# module-pam8320.net
KiCad netlist of a schematic drawn in EAGLE
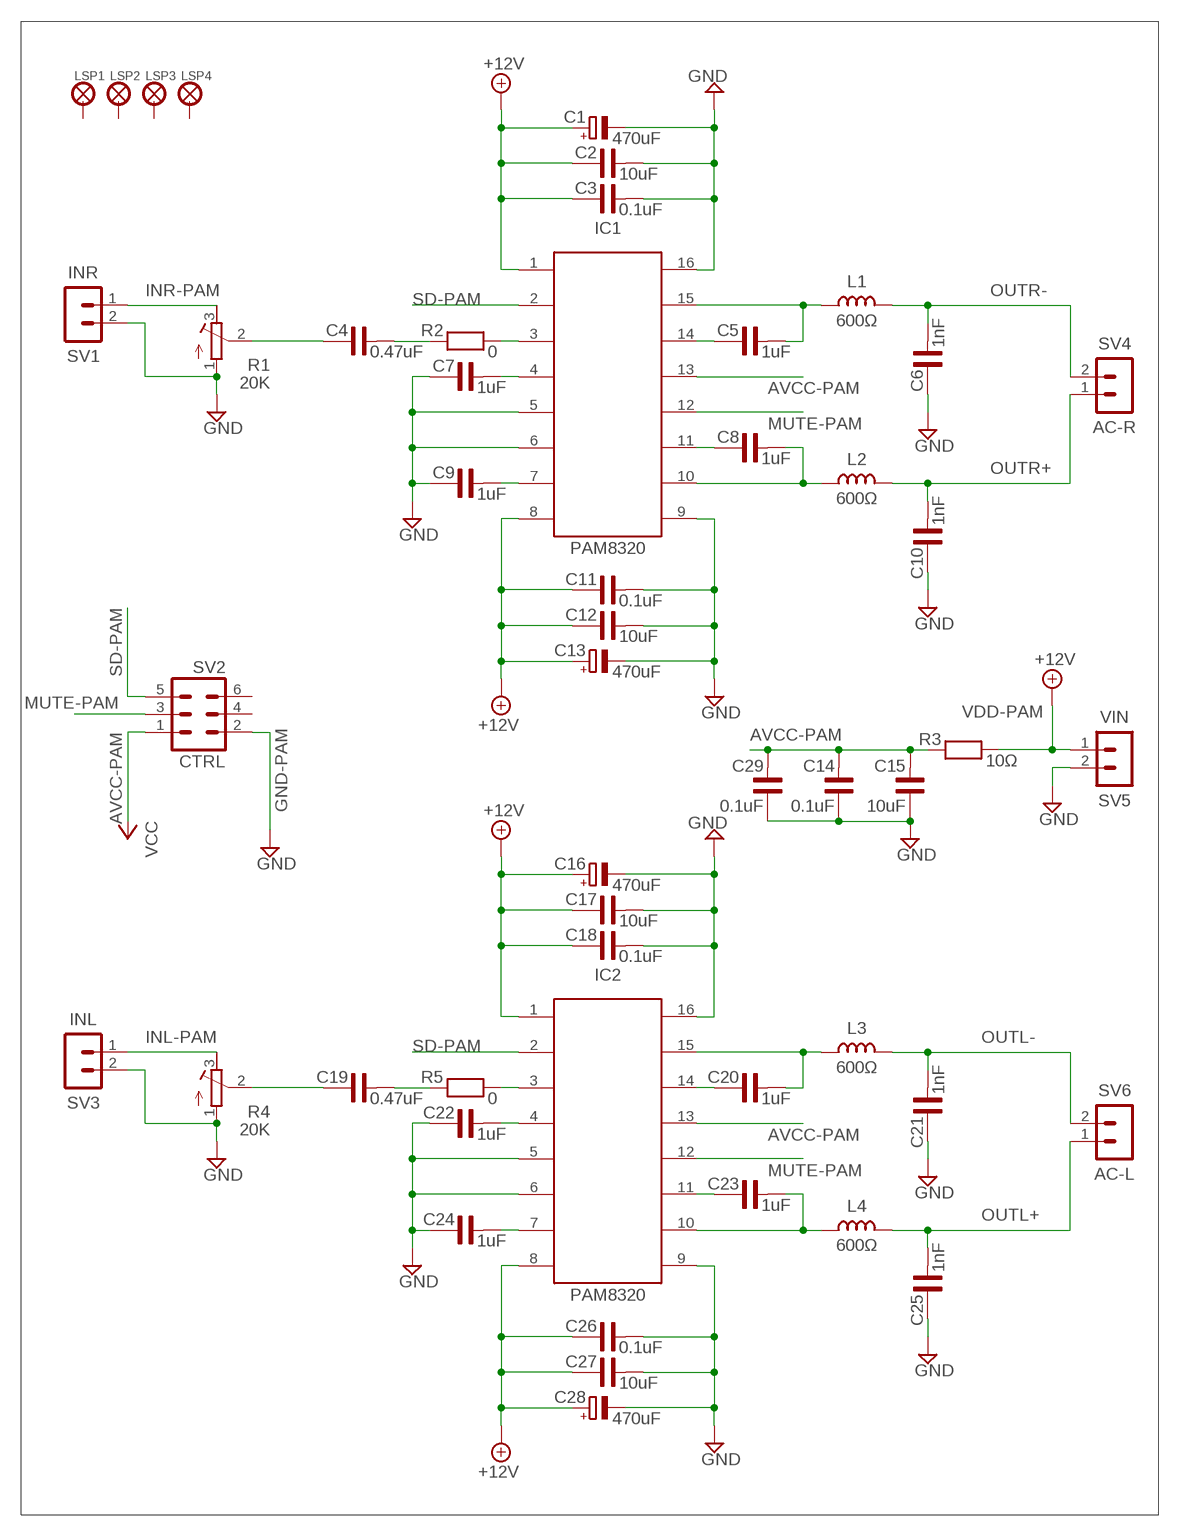
[diagram p0: schematic, sheet 1]

(export (version "E")
  (design (tool "Eeschema 10.0.6"))
  (components
    (comp (ref "C1")
      (value "470uF")
      (footprint "eagle-import:E5-10,5")
      (libsource (lib "eagle-import") (part "CPOL-EUE5-10.5"))
    )
    (comp (ref "C2")
      (value "10uF")
      (footprint "eagle-import:C1206")
      (libsource (lib "eagle-import") (part "C-US1206"))
    )
    (comp (ref "C3")
      (value "0.1uF")
      (footprint "eagle-import:C0805")
      (libsource (lib "eagle-import") (part "C-US0805"))
    )
    (comp (ref "C4")
      (value "0.47uF")
      (footprint "eagle-import:C0805")
      (libsource (lib "eagle-import") (part "C-US0805"))
    )
    (comp (ref "C5")
      (value "1uF")
      (footprint "eagle-import:C1206")
      (libsource (lib "eagle-import") (part "C-US1206"))
    )
    (comp (ref "C6")
      (value "1nF")
      (footprint "eagle-import:C0805")
      (libsource (lib "eagle-import") (part "C-US0805"))
    )
    (comp (ref "C7")
      (value "1uF")
      (footprint "eagle-import:C1206")
      (libsource (lib "eagle-import") (part "C-US1206"))
    )
    (comp (ref "C8")
      (value "1uF")
      (footprint "eagle-import:C1206")
      (libsource (lib "eagle-import") (part "C-US1206"))
    )
    (comp (ref "C9")
      (value "1uF")
      (footprint "eagle-import:C1206")
      (libsource (lib "eagle-import") (part "C-US1206"))
    )
    (comp (ref "C10")
      (value "1nF")
      (footprint "eagle-import:C0805")
      (libsource (lib "eagle-import") (part "C-US0805"))
    )
    (comp (ref "C11")
      (value "0.1uF")
      (footprint "eagle-import:C0805")
      (libsource (lib "eagle-import") (part "C-US0805"))
    )
    (comp (ref "C12")
      (value "10uF")
      (footprint "eagle-import:C1206")
      (libsource (lib "eagle-import") (part "C-US1206"))
    )
    (comp (ref "C13")
      (value "470uF")
      (footprint "eagle-import:E5-10,5")
      (libsource (lib "eagle-import") (part "CPOL-EUE5-10.5"))
    )
    (comp (ref "C14")
      (value "0.1uF")
      (footprint "eagle-import:C0805")
      (libsource (lib "eagle-import") (part "C-US0805"))
    )
    (comp (ref "C15")
      (value "10uF")
      (footprint "eagle-import:C1206")
      (libsource (lib "eagle-import") (part "C-US1206"))
    )
    (comp (ref "C16")
      (value "470uF")
      (footprint "eagle-import:E5-10,5")
      (libsource (lib "eagle-import") (part "CPOL-EUE5-10.5"))
    )
    (comp (ref "C17")
      (value "10uF")
      (footprint "eagle-import:C1206")
      (libsource (lib "eagle-import") (part "C-US1206"))
    )
    (comp (ref "C18")
      (value "0.1uF")
      (footprint "eagle-import:C0805")
      (libsource (lib "eagle-import") (part "C-US0805"))
    )
    (comp (ref "C19")
      (value "0.47uF")
      (footprint "eagle-import:C0805")
      (libsource (lib "eagle-import") (part "C-US0805"))
    )
    (comp (ref "C20")
      (value "1uF")
      (footprint "eagle-import:C1206")
      (libsource (lib "eagle-import") (part "C-US1206"))
    )
    (comp (ref "C21")
      (value "1nF")
      (footprint "eagle-import:C0805")
      (libsource (lib "eagle-import") (part "C-US0805"))
    )
    (comp (ref "C22")
      (value "1uF")
      (footprint "eagle-import:C1206")
      (libsource (lib "eagle-import") (part "C-US1206"))
    )
    (comp (ref "C23")
      (value "1uF")
      (footprint "eagle-import:C1206")
      (libsource (lib "eagle-import") (part "C-US1206"))
    )
    (comp (ref "C24")
      (value "1uF")
      (footprint "eagle-import:C1206")
      (libsource (lib "eagle-import") (part "C-US1206"))
    )
    (comp (ref "C25")
      (value "1nF")
      (footprint "eagle-import:C0805")
      (libsource (lib "eagle-import") (part "C-US0805"))
    )
    (comp (ref "C26")
      (value "0.1uF")
      (footprint "eagle-import:C0805")
      (libsource (lib "eagle-import") (part "C-US0805"))
    )
    (comp (ref "C27")
      (value "10uF")
      (footprint "eagle-import:C1206")
      (libsource (lib "eagle-import") (part "C-US1206"))
    )
    (comp (ref "C28")
      (value "470uF")
      (footprint "eagle-import:E5-10,5")
      (libsource (lib "eagle-import") (part "CPOL-EUE5-10.5"))
    )
    (comp (ref "C29")
      (value "0.1uF")
      (footprint "eagle-import:C0805")
      (libsource (lib "eagle-import") (part "C-US0805"))
    )
    (comp (ref "IC1")
      (value "PAM8320")
      (footprint "eagle-import:SO16")
      (libsource (lib "eagle-import") (part "PAM8320"))
    )
    (comp (ref "IC2")
      (value "PAM8320")
      (footprint "eagle-import:SO16")
      (libsource (lib "eagle-import") (part "PAM8320"))
    )
    (comp (ref "L1")
      (value "600Ω")
      (footprint "eagle-import:L1206")
      (libsource (lib "eagle-import") (part "L-USL1206"))
    )
    (comp (ref "L2")
      (value "600Ω")
      (footprint "eagle-import:L1206")
      (libsource (lib "eagle-import") (part "L-USL1206"))
    )
    (comp (ref "L3")
      (value "600Ω")
      (footprint "eagle-import:L1206")
      (libsource (lib "eagle-import") (part "L-USL1206"))
    )
    (comp (ref "L4")
      (value "600Ω")
      (footprint "eagle-import:L1206")
      (libsource (lib "eagle-import") (part "L-USL1206"))
    )
    (comp (ref "LSP1")
      (value "LSP27")
      (footprint "eagle-import:LSP27")
      (libsource (lib "eagle-import") (part "LSP27"))
    )
    (comp (ref "LSP2")
      (value "LSP27")
      (footprint "eagle-import:LSP27")
      (libsource (lib "eagle-import") (part "LSP27"))
    )
    (comp (ref "LSP3")
      (value "LSP27")
      (footprint "eagle-import:LSP27")
      (libsource (lib "eagle-import") (part "LSP27"))
    )
    (comp (ref "LSP4")
      (value "LSP27")
      (footprint "eagle-import:LSP27")
      (libsource (lib "eagle-import") (part "LSP27"))
    )
    (comp (ref "R1")
      (value "20K")
      (footprint "eagle-import:PV32H")
      (libsource (lib "eagle-import") (part "PV32H"))
    )
    (comp (ref "R2")
      (value "0")
      (footprint "eagle-import:R0805")
      (libsource (lib "eagle-import") (part "R-US0805"))
    )
    (comp (ref "R3")
      (value "10Ω")
      (footprint "eagle-import:R0805")
      (libsource (lib "eagle-import") (part "R-US0805"))
    )
    (comp (ref "R4")
      (value "20K")
      (footprint "eagle-import:PV32H")
      (libsource (lib "eagle-import") (part "PV32H"))
    )
    (comp (ref "R5")
      (value "0")
      (footprint "eagle-import:R0805")
      (libsource (lib "eagle-import") (part "R-US0805"))
    )
    (comp (ref "SV1")
      (value "INR")
      (footprint "eagle-import:MA02-1-GREEN")
      (libsource (lib "eagle-import") (part "MA02-1GREEN"))
    )
    (comp (ref "SV2")
      (value "CTRL")
      (footprint "eagle-import:MA03-2")
      (libsource (lib "eagle-import") (part "MA03-2PL"))
    )
    (comp (ref "SV3")
      (value "INL")
      (footprint "eagle-import:MA02-1-GREEN")
      (libsource (lib "eagle-import") (part "MA02-1GREEN"))
    )
    (comp (ref "SV4")
      (value "AC-R")
      (footprint "eagle-import:MA02-1-GREEN")
      (libsource (lib "eagle-import") (part "MA02-1GREEN"))
    )
    (comp (ref "SV5")
      (value "VIN")
      (footprint "eagle-import:MA02-1-GREEN")
      (libsource (lib "eagle-import") (part "MA02-1GREEN"))
    )
    (comp (ref "SV6")
      (value "AC-L")
      (footprint "eagle-import:MA02-1-GREEN")
      (libsource (lib "eagle-import") (part "MA02-1GREEN"))
    )
  )
  (nets
    (net (code "1") (name "+12V") (class "Default")
      (node (ref "C1") (pin "+") (pinfunction "+_+") (pintype "passive"))
      (node (ref "C11") (pin "1") (pinfunction "1_1") (pintype "passive"))
      (node (ref "C12") (pin "1") (pinfunction "1_1") (pintype "passive"))
      (node (ref "C13") (pin "+") (pinfunction "+_+") (pintype "passive"))
      (node (ref "C16") (pin "+") (pinfunction "+_+") (pintype "passive"))
      (node (ref "C17") (pin "1") (pinfunction "1_1") (pintype "passive"))
      (node (ref "C18") (pin "1") (pinfunction "1_1") (pintype "passive"))
      (node (ref "C2") (pin "1") (pinfunction "1_1") (pintype "passive"))
      (node (ref "C26") (pin "1") (pinfunction "1_1") (pintype "passive"))
      (node (ref "C27") (pin "1") (pinfunction "1_1") (pintype "passive"))
      (node (ref "C28") (pin "+") (pinfunction "+_+") (pintype "passive"))
      (node (ref "C3") (pin "1") (pinfunction "1_1") (pintype "passive"))
      (node (ref "IC1") (pin "1") (pinfunction "P$1_1") (pintype "bidirectional"))
      (node (ref "IC1") (pin "8") (pinfunction "P$8_8") (pintype "bidirectional"))
      (node (ref "IC2") (pin "1") (pinfunction "P$1_1") (pintype "bidirectional"))
      (node (ref "IC2") (pin "8") (pinfunction "P$8_8") (pintype "bidirectional"))
      (node (ref "R3") (pin "2") (pinfunction "2_2") (pintype "passive"))
      (node (ref "SV5") (pin "1") (pinfunction "1_1") (pintype "passive"))
    )
    (net (code "2") (name "/INL-PAM") (class "Default")
      (node (ref "R4") (pin "3") (pinfunction "3_3") (pintype "passive"))
      (node (ref "SV3") (pin "1") (pinfunction "1_1") (pintype "passive"))
    )
    (net (code "3") (name "/INR-PAM") (class "Default")
      (node (ref "R1") (pin "3") (pinfunction "3_3") (pintype "passive"))
      (node (ref "SV1") (pin "1") (pinfunction "1_1") (pintype "passive"))
    )
    (net (code "4") (name "/MUTE-PAM") (class "Default")
      (node (ref "IC1") (pin "12") (pinfunction "P$12_12") (pintype "bidirectional"))
      (node (ref "IC2") (pin "12") (pinfunction "P$12_12") (pintype "bidirectional"))
      (node (ref "SV2") (pin "3") (pinfunction "3_3") (pintype "passive"))
    )
    (net (code "5") (name "/OUTL+") (class "Default")
      (node (ref "C25") (pin "2") (pinfunction "2_2") (pintype "passive"))
      (node (ref "L4") (pin "2") (pinfunction "2_2") (pintype "passive"))
      (node (ref "SV6") (pin "1") (pinfunction "1_1") (pintype "passive"))
    )
    (net (code "6") (name "/OUTL-") (class "Default")
      (node (ref "C21") (pin "2") (pinfunction "2_2") (pintype "passive"))
      (node (ref "L3") (pin "2") (pinfunction "2_2") (pintype "passive"))
      (node (ref "SV6") (pin "2") (pinfunction "2_2") (pintype "passive"))
    )
    (net (code "7") (name "/OUTR+") (class "Default")
      (node (ref "C10") (pin "2") (pinfunction "2_2") (pintype "passive"))
      (node (ref "L2") (pin "2") (pinfunction "2_2") (pintype "passive"))
      (node (ref "SV4") (pin "1") (pinfunction "1_1") (pintype "passive"))
    )
    (net (code "8") (name "/OUTR-") (class "Default")
      (node (ref "C6") (pin "2") (pinfunction "2_2") (pintype "passive"))
      (node (ref "L1") (pin "2") (pinfunction "2_2") (pintype "passive"))
      (node (ref "SV4") (pin "2") (pinfunction "2_2") (pintype "passive"))
    )
    (net (code "9") (name "/SD-PAM") (class "Default")
      (node (ref "IC1") (pin "2") (pinfunction "P$2_2") (pintype "bidirectional"))
      (node (ref "IC2") (pin "2") (pinfunction "P$2_2") (pintype "bidirectional"))
      (node (ref "SV2") (pin "5") (pinfunction "5_5") (pintype "passive"))
    )
    (net (code "10") (name "GND") (class "Default")
      (node (ref "C1") (pin "-") (pinfunction "-_-") (pintype "passive"))
      (node (ref "C10") (pin "1") (pinfunction "1_1") (pintype "passive"))
      (node (ref "C11") (pin "2") (pinfunction "2_2") (pintype "passive"))
      (node (ref "C12") (pin "2") (pinfunction "2_2") (pintype "passive"))
      (node (ref "C13") (pin "-") (pinfunction "-_-") (pintype "passive"))
      (node (ref "C14") (pin "1") (pinfunction "1_1") (pintype "passive"))
      (node (ref "C15") (pin "1") (pinfunction "1_1") (pintype "passive"))
      (node (ref "C16") (pin "-") (pinfunction "-_-") (pintype "passive"))
      (node (ref "C17") (pin "2") (pinfunction "2_2") (pintype "passive"))
      (node (ref "C18") (pin "2") (pinfunction "2_2") (pintype "passive"))
      (node (ref "C2") (pin "2") (pinfunction "2_2") (pintype "passive"))
      (node (ref "C21") (pin "1") (pinfunction "1_1") (pintype "passive"))
      (node (ref "C22") (pin "1") (pinfunction "1_1") (pintype "passive"))
      (node (ref "C24") (pin "1") (pinfunction "1_1") (pintype "passive"))
      (node (ref "C25") (pin "1") (pinfunction "1_1") (pintype "passive"))
      (node (ref "C26") (pin "2") (pinfunction "2_2") (pintype "passive"))
      (node (ref "C27") (pin "2") (pinfunction "2_2") (pintype "passive"))
      (node (ref "C28") (pin "-") (pinfunction "-_-") (pintype "passive"))
      (node (ref "C29") (pin "1") (pinfunction "1_1") (pintype "passive"))
      (node (ref "C3") (pin "2") (pinfunction "2_2") (pintype "passive"))
      (node (ref "C6") (pin "1") (pinfunction "1_1") (pintype "passive"))
      (node (ref "C7") (pin "1") (pinfunction "1_1") (pintype "passive"))
      (node (ref "C9") (pin "1") (pinfunction "1_1") (pintype "passive"))
      (node (ref "IC1") (pin "16") (pinfunction "P$16_16") (pintype "bidirectional"))
      (node (ref "IC1") (pin "5") (pinfunction "P$5_5") (pintype "bidirectional"))
      (node (ref "IC1") (pin "6") (pinfunction "P$6_6") (pintype "bidirectional"))
      (node (ref "IC1") (pin "9") (pinfunction "P$9_9") (pintype "bidirectional"))
      (node (ref "IC2") (pin "16") (pinfunction "P$16_16") (pintype "bidirectional"))
      (node (ref "IC2") (pin "5") (pinfunction "P$5_5") (pintype "bidirectional"))
      (node (ref "IC2") (pin "6") (pinfunction "P$6_6") (pintype "bidirectional"))
      (node (ref "IC2") (pin "9") (pinfunction "P$9_9") (pintype "bidirectional"))
      (node (ref "R1") (pin "1") (pinfunction "1_1") (pintype "passive"))
      (node (ref "R4") (pin "1") (pinfunction "1_1") (pintype "passive"))
      (node (ref "SV1") (pin "2") (pinfunction "2_2") (pintype "passive"))
      (node (ref "SV2") (pin "2") (pinfunction "2_2") (pintype "passive"))
      (node (ref "SV3") (pin "2") (pinfunction "2_2") (pintype "passive"))
      (node (ref "SV5") (pin "2") (pinfunction "2_2") (pintype "passive"))
    )
    (net (code "11") (name "Net-(C4-Pad1)") (class "Default")
      (node (ref "C4") (pin "1") (pinfunction "1_1") (pintype "passive"))
      (node (ref "R1") (pin "2") (pinfunction "2_2") (pintype "passive"))
    )
    (net (code "12") (name "Net-(C4-Pad2)") (class "Default")
      (node (ref "C4") (pin "2") (pinfunction "2_2") (pintype "passive"))
      (node (ref "R2") (pin "1") (pinfunction "1_1") (pintype "passive"))
    )
    (net (code "13") (name "Net-(C19-Pad1)") (class "Default")
      (node (ref "C19") (pin "1") (pinfunction "1_1") (pintype "passive"))
      (node (ref "R4") (pin "2") (pinfunction "2_2") (pintype "passive"))
    )
    (net (code "14") (name "Net-(C19-Pad2)") (class "Default")
      (node (ref "C19") (pin "2") (pinfunction "2_2") (pintype "passive"))
      (node (ref "R5") (pin "1") (pinfunction "1_1") (pintype "passive"))
    )
    (net (code "15") (name "Net-(IC1-P$3)") (class "Default")
      (node (ref "IC1") (pin "3") (pinfunction "P$3_3") (pintype "bidirectional"))
      (node (ref "R2") (pin "2") (pinfunction "2_2") (pintype "passive"))
    )
    (net (code "16") (name "Net-(IC1-P$4)") (class "Default")
      (node (ref "C7") (pin "2") (pinfunction "2_2") (pintype "passive"))
      (node (ref "IC1") (pin "4") (pinfunction "P$4_4") (pintype "bidirectional"))
    )
    (net (code "17") (name "Net-(IC1-P$7)") (class "Default")
      (node (ref "C9") (pin "2") (pinfunction "2_2") (pintype "passive"))
      (node (ref "IC1") (pin "7") (pinfunction "P$7_7") (pintype "bidirectional"))
    )
    (net (code "18") (name "Net-(IC1-P$10)") (class "Default")
      (node (ref "C8") (pin "2") (pinfunction "2_2") (pintype "passive"))
      (node (ref "IC1") (pin "10") (pinfunction "P$10_10") (pintype "bidirectional"))
      (node (ref "L2") (pin "1") (pinfunction "1_1") (pintype "passive"))
    )
    (net (code "19") (name "Net-(IC1-P$11)") (class "Default")
      (node (ref "C8") (pin "1") (pinfunction "1_1") (pintype "passive"))
      (node (ref "IC1") (pin "11") (pinfunction "P$11_11") (pintype "bidirectional"))
    )
    (net (code "20") (name "Net-(IC1-P$14)") (class "Default")
      (node (ref "C5") (pin "1") (pinfunction "1_1") (pintype "passive"))
      (node (ref "IC1") (pin "14") (pinfunction "P$14_14") (pintype "bidirectional"))
    )
    (net (code "21") (name "Net-(IC1-P$15)") (class "Default")
      (node (ref "C5") (pin "2") (pinfunction "2_2") (pintype "passive"))
      (node (ref "IC1") (pin "15") (pinfunction "P$15_15") (pintype "bidirectional"))
      (node (ref "L1") (pin "1") (pinfunction "1_1") (pintype "passive"))
    )
    (net (code "22") (name "Net-(IC2-P$3)") (class "Default")
      (node (ref "IC2") (pin "3") (pinfunction "P$3_3") (pintype "bidirectional"))
      (node (ref "R5") (pin "2") (pinfunction "2_2") (pintype "passive"))
    )
    (net (code "23") (name "Net-(IC2-P$4)") (class "Default")
      (node (ref "C22") (pin "2") (pinfunction "2_2") (pintype "passive"))
      (node (ref "IC2") (pin "4") (pinfunction "P$4_4") (pintype "bidirectional"))
    )
    (net (code "24") (name "Net-(IC2-P$7)") (class "Default")
      (node (ref "C24") (pin "2") (pinfunction "2_2") (pintype "passive"))
      (node (ref "IC2") (pin "7") (pinfunction "P$7_7") (pintype "bidirectional"))
    )
    (net (code "25") (name "Net-(IC2-P$10)") (class "Default")
      (node (ref "C23") (pin "2") (pinfunction "2_2") (pintype "passive"))
      (node (ref "IC2") (pin "10") (pinfunction "P$10_10") (pintype "bidirectional"))
      (node (ref "L4") (pin "1") (pinfunction "1_1") (pintype "passive"))
    )
    (net (code "26") (name "Net-(IC2-P$11)") (class "Default")
      (node (ref "C23") (pin "1") (pinfunction "1_1") (pintype "passive"))
      (node (ref "IC2") (pin "11") (pinfunction "P$11_11") (pintype "bidirectional"))
    )
    (net (code "27") (name "Net-(IC2-P$14)") (class "Default")
      (node (ref "C20") (pin "1") (pinfunction "1_1") (pintype "passive"))
      (node (ref "IC2") (pin "14") (pinfunction "P$14_14") (pintype "bidirectional"))
    )
    (net (code "28") (name "Net-(IC2-P$15)") (class "Default")
      (node (ref "C20") (pin "2") (pinfunction "2_2") (pintype "passive"))
      (node (ref "IC2") (pin "15") (pinfunction "P$15_15") (pintype "bidirectional"))
      (node (ref "L3") (pin "1") (pinfunction "1_1") (pintype "passive"))
    )
    (net (code "29") (name "VCC") (class "Default")
      (node (ref "C14") (pin "2") (pinfunction "2_2") (pintype "passive"))
      (node (ref "C15") (pin "2") (pinfunction "2_2") (pintype "passive"))
      (node (ref "C29") (pin "2") (pinfunction "2_2") (pintype "passive"))
      (node (ref "IC1") (pin "13") (pinfunction "P$13_13") (pintype "bidirectional"))
      (node (ref "IC2") (pin "13") (pinfunction "P$13_13") (pintype "bidirectional"))
      (node (ref "R3") (pin "1") (pinfunction "1_1") (pintype "passive"))
      (node (ref "SV2") (pin "1") (pinfunction "1_1") (pintype "passive"))
    )
    (net (code "30") (name "unconnected-(LSP1-PadMP)") (class "Default")
      (node (ref "LSP1") (pin "MP") (pinfunction "MP_MP") (pintype "passive"))
    )
    (net (code "31") (name "unconnected-(LSP2-PadMP)") (class "Default")
      (node (ref "LSP2") (pin "MP") (pinfunction "MP_MP") (pintype "passive"))
    )
    (net (code "32") (name "unconnected-(LSP3-PadMP)") (class "Default")
      (node (ref "LSP3") (pin "MP") (pinfunction "MP_MP") (pintype "passive"))
    )
    (net (code "33") (name "unconnected-(LSP4-PadMP)") (class "Default")
      (node (ref "LSP4") (pin "MP") (pinfunction "MP_MP") (pintype "passive"))
    )
    (net (code "34") (name "unconnected-(SV2-Pad4)") (class "Default")
      (node (ref "SV2") (pin "4") (pinfunction "4_4") (pintype "passive"))
    )
    (net (code "35") (name "unconnected-(SV2-Pad6)") (class "Default")
      (node (ref "SV2") (pin "6") (pinfunction "6_6") (pintype "passive"))
    )
  )
)
